# Matrix.net
KiCad netlist of a schematic drawn in Altium Designer
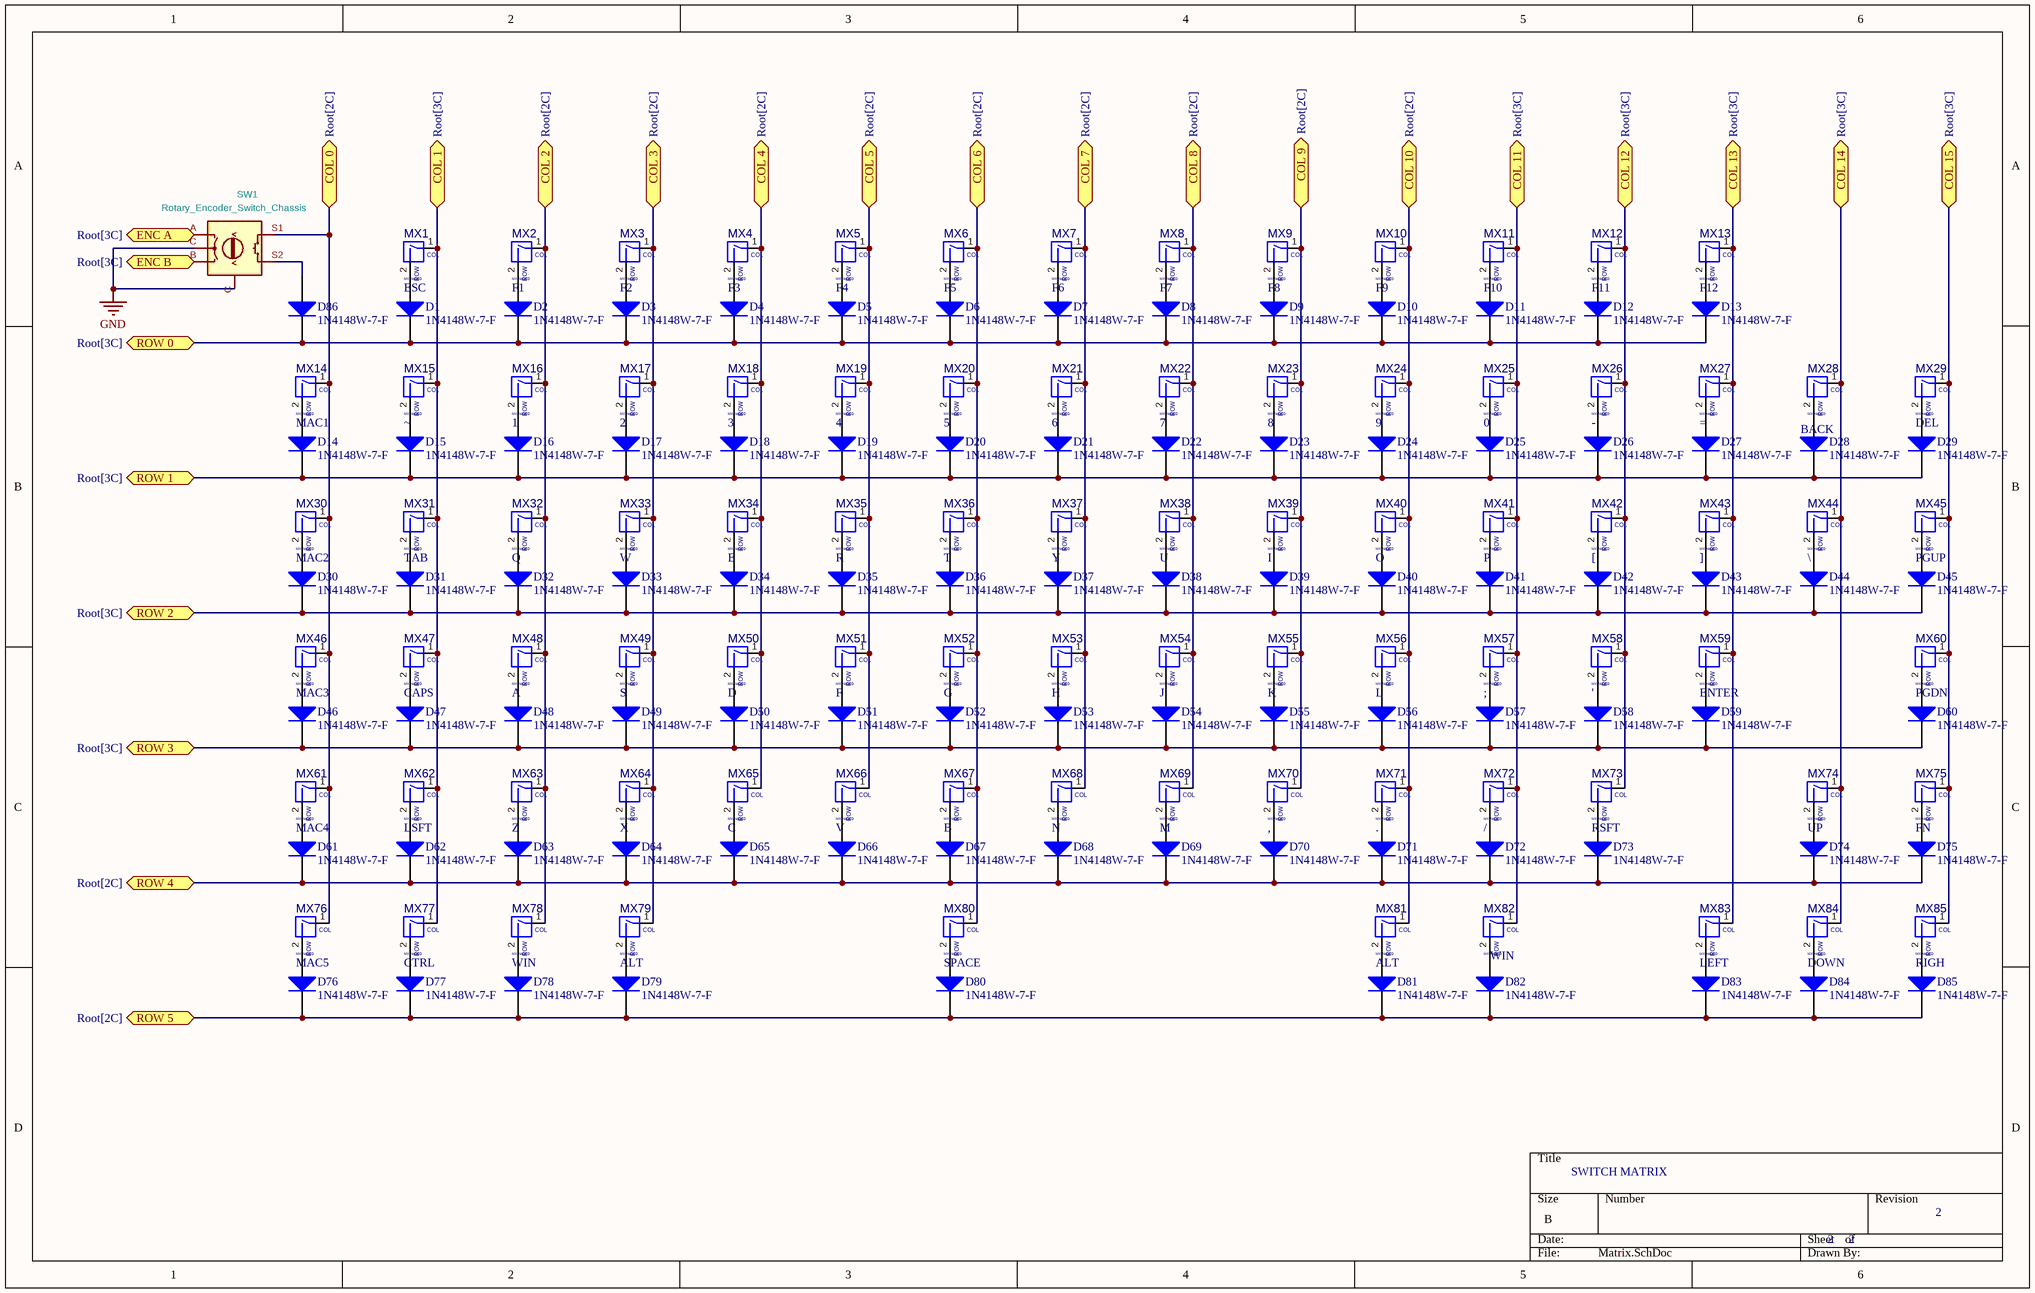
[diagram p0: Matrix.SchDoc]

(export (version "E")
  (design (tool "Eeschema 10.0.6"))
  (components
    (comp (ref "D1")
      (value "1N4148W-7-F")
      (footprint "DIOD-SOD123-2_V")
      (description "Rectifier Diode, 1 Phase, 1 Element, 0.15A, 100V V(RRM), Silicon")
      (libsource (lib "Daniel Hai") (part "D-AK-2"))
    )
    (comp (ref "D2")
      (value "1N4148W-7-F")
      (footprint "DIOD-SOD123-2_V")
      (description "Rectifier Diode, 1 Phase, 1 Element, 0.15A, 100V V(RRM), Silicon")
      (libsource (lib "Daniel Hai") (part "D-AK-2"))
    )
    (comp (ref "D3")
      (value "1N4148W-7-F")
      (footprint "DIOD-SOD123-2_V")
      (description "Rectifier Diode, 1 Phase, 1 Element, 0.15A, 100V V(RRM), Silicon")
      (libsource (lib "Daniel Hai") (part "D-AK-2"))
    )
    (comp (ref "D4")
      (value "1N4148W-7-F")
      (footprint "DIOD-SOD123-2_V")
      (description "Rectifier Diode, 1 Phase, 1 Element, 0.15A, 100V V(RRM), Silicon")
      (libsource (lib "Daniel Hai") (part "D-AK-2"))
    )
    (comp (ref "D5")
      (value "1N4148W-7-F")
      (footprint "DIOD-SOD123-2_V")
      (description "Rectifier Diode, 1 Phase, 1 Element, 0.15A, 100V V(RRM), Silicon")
      (libsource (lib "Daniel Hai") (part "D-AK-2"))
    )
    (comp (ref "D6")
      (value "1N4148W-7-F")
      (footprint "DIOD-SOD123-2_V")
      (description "Rectifier Diode, 1 Phase, 1 Element, 0.15A, 100V V(RRM), Silicon")
      (libsource (lib "Daniel Hai") (part "D-AK-2"))
    )
    (comp (ref "D7")
      (value "1N4148W-7-F")
      (footprint "DIOD-SOD123-2_V")
      (description "Rectifier Diode, 1 Phase, 1 Element, 0.15A, 100V V(RRM), Silicon")
      (libsource (lib "Daniel Hai") (part "D-AK-2"))
    )
    (comp (ref "D8")
      (value "1N4148W-7-F")
      (footprint "DIOD-SOD123-2_V")
      (description "Rectifier Diode, 1 Phase, 1 Element, 0.15A, 100V V(RRM), Silicon")
      (libsource (lib "Daniel Hai") (part "D-AK-2"))
    )
    (comp (ref "D9")
      (value "1N4148W-7-F")
      (footprint "DIOD-SOD123-2_V")
      (description "Rectifier Diode, 1 Phase, 1 Element, 0.15A, 100V V(RRM), Silicon")
      (libsource (lib "Daniel Hai") (part "D-AK-2"))
    )
    (comp (ref "D10")
      (value "1N4148W-7-F")
      (footprint "DIOD-SOD123-2_V")
      (description "Rectifier Diode, 1 Phase, 1 Element, 0.15A, 100V V(RRM), Silicon")
      (libsource (lib "Daniel Hai") (part "D-AK-2"))
    )
    (comp (ref "D11")
      (value "1N4148W-7-F")
      (footprint "DIOD-SOD123-2_V")
      (description "Rectifier Diode, 1 Phase, 1 Element, 0.15A, 100V V(RRM), Silicon")
      (libsource (lib "Daniel Hai") (part "D-AK-2"))
    )
    (comp (ref "D12")
      (value "1N4148W-7-F")
      (footprint "DIOD-SOD123-2_V")
      (description "Rectifier Diode, 1 Phase, 1 Element, 0.15A, 100V V(RRM), Silicon")
      (libsource (lib "Daniel Hai") (part "D-AK-2"))
    )
    (comp (ref "D13")
      (value "1N4148W-7-F")
      (footprint "DIOD-SOD123-2_V")
      (description "Rectifier Diode, 1 Phase, 1 Element, 0.15A, 100V V(RRM), Silicon")
      (libsource (lib "Daniel Hai") (part "D-AK-2"))
    )
    (comp (ref "D14")
      (value "1N4148W-7-F")
      (footprint "DIOD-SOD123-2_V")
      (description "Rectifier Diode, 1 Phase, 1 Element, 0.15A, 100V V(RRM), Silicon")
      (libsource (lib "Daniel Hai") (part "D-AK-2"))
    )
    (comp (ref "D15")
      (value "1N4148W-7-F")
      (footprint "DIOD-SOD123-2_V")
      (description "Rectifier Diode, 1 Phase, 1 Element, 0.15A, 100V V(RRM), Silicon")
      (libsource (lib "Daniel Hai") (part "D-AK-2"))
    )
    (comp (ref "D16")
      (value "1N4148W-7-F")
      (footprint "DIOD-SOD123-2_V")
      (description "Rectifier Diode, 1 Phase, 1 Element, 0.15A, 100V V(RRM), Silicon")
      (libsource (lib "Daniel Hai") (part "D-AK-2"))
    )
    (comp (ref "D17")
      (value "1N4148W-7-F")
      (footprint "DIOD-SOD123-2_V")
      (description "Rectifier Diode, 1 Phase, 1 Element, 0.15A, 100V V(RRM), Silicon")
      (libsource (lib "Daniel Hai") (part "D-AK-2"))
    )
    (comp (ref "D18")
      (value "1N4148W-7-F")
      (footprint "DIOD-SOD123-2_V")
      (description "Rectifier Diode, 1 Phase, 1 Element, 0.15A, 100V V(RRM), Silicon")
      (libsource (lib "Daniel Hai") (part "D-AK-2"))
    )
    (comp (ref "D19")
      (value "1N4148W-7-F")
      (footprint "DIOD-SOD123-2_V")
      (description "Rectifier Diode, 1 Phase, 1 Element, 0.15A, 100V V(RRM), Silicon")
      (libsource (lib "Daniel Hai") (part "D-AK-2"))
    )
    (comp (ref "D20")
      (value "1N4148W-7-F")
      (footprint "DIOD-SOD123-2_V")
      (description "Rectifier Diode, 1 Phase, 1 Element, 0.15A, 100V V(RRM), Silicon")
      (libsource (lib "Daniel Hai") (part "D-AK-2"))
    )
    (comp (ref "D21")
      (value "1N4148W-7-F")
      (footprint "DIOD-SOD123-2_V")
      (description "Rectifier Diode, 1 Phase, 1 Element, 0.15A, 100V V(RRM), Silicon")
      (libsource (lib "Daniel Hai") (part "D-AK-2"))
    )
    (comp (ref "D22")
      (value "1N4148W-7-F")
      (footprint "DIOD-SOD123-2_V")
      (description "Rectifier Diode, 1 Phase, 1 Element, 0.15A, 100V V(RRM), Silicon")
      (libsource (lib "Daniel Hai") (part "D-AK-2"))
    )
    (comp (ref "D23")
      (value "1N4148W-7-F")
      (footprint "DIOD-SOD123-2_V")
      (description "Rectifier Diode, 1 Phase, 1 Element, 0.15A, 100V V(RRM), Silicon")
      (libsource (lib "Daniel Hai") (part "D-AK-2"))
    )
    (comp (ref "D24")
      (value "1N4148W-7-F")
      (footprint "DIOD-SOD123-2_V")
      (description "Rectifier Diode, 1 Phase, 1 Element, 0.15A, 100V V(RRM), Silicon")
      (libsource (lib "Daniel Hai") (part "D-AK-2"))
    )
    (comp (ref "D25")
      (value "1N4148W-7-F")
      (footprint "DIOD-SOD123-2_V")
      (description "Rectifier Diode, 1 Phase, 1 Element, 0.15A, 100V V(RRM), Silicon")
      (libsource (lib "Daniel Hai") (part "D-AK-2"))
    )
    (comp (ref "D26")
      (value "1N4148W-7-F")
      (footprint "DIOD-SOD123-2_V")
      (description "Rectifier Diode, 1 Phase, 1 Element, 0.15A, 100V V(RRM), Silicon")
      (libsource (lib "Daniel Hai") (part "D-AK-2"))
    )
    (comp (ref "D27")
      (value "1N4148W-7-F")
      (footprint "DIOD-SOD123-2_V")
      (description "Rectifier Diode, 1 Phase, 1 Element, 0.15A, 100V V(RRM), Silicon")
      (libsource (lib "Daniel Hai") (part "D-AK-2"))
    )
    (comp (ref "D28")
      (value "1N4148W-7-F")
      (footprint "DIOD-SOD123-2_V")
      (description "Rectifier Diode, 1 Phase, 1 Element, 0.15A, 100V V(RRM), Silicon")
      (libsource (lib "Daniel Hai") (part "D-AK-2"))
    )
    (comp (ref "D29")
      (value "1N4148W-7-F")
      (footprint "DIOD-SOD123-2_V")
      (description "Rectifier Diode, 1 Phase, 1 Element, 0.15A, 100V V(RRM), Silicon")
      (libsource (lib "Daniel Hai") (part "D-AK-2"))
    )
    (comp (ref "D30")
      (value "1N4148W-7-F")
      (footprint "DIOD-SOD123-2_V")
      (description "Rectifier Diode, 1 Phase, 1 Element, 0.15A, 100V V(RRM), Silicon")
      (libsource (lib "Daniel Hai") (part "D-AK-2"))
    )
    (comp (ref "D31")
      (value "1N4148W-7-F")
      (footprint "DIOD-SOD123-2_V")
      (description "Rectifier Diode, 1 Phase, 1 Element, 0.15A, 100V V(RRM), Silicon")
      (libsource (lib "Daniel Hai") (part "D-AK-2"))
    )
    (comp (ref "D32")
      (value "1N4148W-7-F")
      (footprint "DIOD-SOD123-2_V")
      (description "Rectifier Diode, 1 Phase, 1 Element, 0.15A, 100V V(RRM), Silicon")
      (libsource (lib "Daniel Hai") (part "D-AK-2"))
    )
    (comp (ref "D33")
      (value "1N4148W-7-F")
      (footprint "DIOD-SOD123-2_V")
      (description "Rectifier Diode, 1 Phase, 1 Element, 0.15A, 100V V(RRM), Silicon")
      (libsource (lib "Daniel Hai") (part "D-AK-2"))
    )
    (comp (ref "D34")
      (value "1N4148W-7-F")
      (footprint "DIOD-SOD123-2_V")
      (description "Rectifier Diode, 1 Phase, 1 Element, 0.15A, 100V V(RRM), Silicon")
      (libsource (lib "Daniel Hai") (part "D-AK-2"))
    )
    (comp (ref "D35")
      (value "1N4148W-7-F")
      (footprint "DIOD-SOD123-2_V")
      (description "Rectifier Diode, 1 Phase, 1 Element, 0.15A, 100V V(RRM), Silicon")
      (libsource (lib "Daniel Hai") (part "D-AK-2"))
    )
    (comp (ref "D36")
      (value "1N4148W-7-F")
      (footprint "DIOD-SOD123-2_V")
      (description "Rectifier Diode, 1 Phase, 1 Element, 0.15A, 100V V(RRM), Silicon")
      (libsource (lib "Daniel Hai") (part "D-AK-2"))
    )
    (comp (ref "D37")
      (value "1N4148W-7-F")
      (footprint "DIOD-SOD123-2_V")
      (description "Rectifier Diode, 1 Phase, 1 Element, 0.15A, 100V V(RRM), Silicon")
      (libsource (lib "Daniel Hai") (part "D-AK-2"))
    )
    (comp (ref "D38")
      (value "1N4148W-7-F")
      (footprint "DIOD-SOD123-2_V")
      (description "Rectifier Diode, 1 Phase, 1 Element, 0.15A, 100V V(RRM), Silicon")
      (libsource (lib "Daniel Hai") (part "D-AK-2"))
    )
    (comp (ref "D39")
      (value "1N4148W-7-F")
      (footprint "DIOD-SOD123-2_V")
      (description "Rectifier Diode, 1 Phase, 1 Element, 0.15A, 100V V(RRM), Silicon")
      (libsource (lib "Daniel Hai") (part "D-AK-2"))
    )
    (comp (ref "D40")
      (value "1N4148W-7-F")
      (footprint "DIOD-SOD123-2_V")
      (description "Rectifier Diode, 1 Phase, 1 Element, 0.15A, 100V V(RRM), Silicon")
      (libsource (lib "Daniel Hai") (part "D-AK-2"))
    )
    (comp (ref "D41")
      (value "1N4148W-7-F")
      (footprint "DIOD-SOD123-2_V")
      (description "Rectifier Diode, 1 Phase, 1 Element, 0.15A, 100V V(RRM), Silicon")
      (libsource (lib "Daniel Hai") (part "D-AK-2"))
    )
    (comp (ref "D42")
      (value "1N4148W-7-F")
      (footprint "DIOD-SOD123-2_V")
      (description "Rectifier Diode, 1 Phase, 1 Element, 0.15A, 100V V(RRM), Silicon")
      (libsource (lib "Daniel Hai") (part "D-AK-2"))
    )
    (comp (ref "D43")
      (value "1N4148W-7-F")
      (footprint "DIOD-SOD123-2_V")
      (description "Rectifier Diode, 1 Phase, 1 Element, 0.15A, 100V V(RRM), Silicon")
      (libsource (lib "Daniel Hai") (part "D-AK-2"))
    )
    (comp (ref "D44")
      (value "1N4148W-7-F")
      (footprint "DIOD-SOD123-2_V")
      (description "Rectifier Diode, 1 Phase, 1 Element, 0.15A, 100V V(RRM), Silicon")
      (libsource (lib "Daniel Hai") (part "D-AK-2"))
    )
    (comp (ref "D45")
      (value "1N4148W-7-F")
      (footprint "DIOD-SOD123-2_V")
      (description "Rectifier Diode, 1 Phase, 1 Element, 0.15A, 100V V(RRM), Silicon")
      (libsource (lib "Daniel Hai") (part "D-AK-2"))
    )
    (comp (ref "D46")
      (value "1N4148W-7-F")
      (footprint "DIOD-SOD123-2_V")
      (description "Rectifier Diode, 1 Phase, 1 Element, 0.15A, 100V V(RRM), Silicon")
      (libsource (lib "Daniel Hai") (part "D-AK-2"))
    )
    (comp (ref "D47")
      (value "1N4148W-7-F")
      (footprint "DIOD-SOD123-2_V")
      (description "Rectifier Diode, 1 Phase, 1 Element, 0.15A, 100V V(RRM), Silicon")
      (libsource (lib "Daniel Hai") (part "D-AK-2"))
    )
    (comp (ref "D48")
      (value "1N4148W-7-F")
      (footprint "DIOD-SOD123-2_V")
      (description "Rectifier Diode, 1 Phase, 1 Element, 0.15A, 100V V(RRM), Silicon")
      (libsource (lib "Daniel Hai") (part "D-AK-2"))
    )
    (comp (ref "D49")
      (value "1N4148W-7-F")
      (footprint "DIOD-SOD123-2_V")
      (description "Rectifier Diode, 1 Phase, 1 Element, 0.15A, 100V V(RRM), Silicon")
      (libsource (lib "Daniel Hai") (part "D-AK-2"))
    )
    (comp (ref "D50")
      (value "1N4148W-7-F")
      (footprint "DIOD-SOD123-2_V")
      (description "Rectifier Diode, 1 Phase, 1 Element, 0.15A, 100V V(RRM), Silicon")
      (libsource (lib "Daniel Hai") (part "D-AK-2"))
    )
    (comp (ref "D51")
      (value "1N4148W-7-F")
      (footprint "DIOD-SOD123-2_V")
      (description "Rectifier Diode, 1 Phase, 1 Element, 0.15A, 100V V(RRM), Silicon")
      (libsource (lib "Daniel Hai") (part "D-AK-2"))
    )
    (comp (ref "D52")
      (value "1N4148W-7-F")
      (footprint "DIOD-SOD123-2_V")
      (description "Rectifier Diode, 1 Phase, 1 Element, 0.15A, 100V V(RRM), Silicon")
      (libsource (lib "Daniel Hai") (part "D-AK-2"))
    )
    (comp (ref "D53")
      (value "1N4148W-7-F")
      (footprint "DIOD-SOD123-2_V")
      (description "Rectifier Diode, 1 Phase, 1 Element, 0.15A, 100V V(RRM), Silicon")
      (libsource (lib "Daniel Hai") (part "D-AK-2"))
    )
    (comp (ref "D54")
      (value "1N4148W-7-F")
      (footprint "DIOD-SOD123-2_V")
      (description "Rectifier Diode, 1 Phase, 1 Element, 0.15A, 100V V(RRM), Silicon")
      (libsource (lib "Daniel Hai") (part "D-AK-2"))
    )
    (comp (ref "D55")
      (value "1N4148W-7-F")
      (footprint "DIOD-SOD123-2_V")
      (description "Rectifier Diode, 1 Phase, 1 Element, 0.15A, 100V V(RRM), Silicon")
      (libsource (lib "Daniel Hai") (part "D-AK-2"))
    )
    (comp (ref "D56")
      (value "1N4148W-7-F")
      (footprint "DIOD-SOD123-2_V")
      (description "Rectifier Diode, 1 Phase, 1 Element, 0.15A, 100V V(RRM), Silicon")
      (libsource (lib "Daniel Hai") (part "D-AK-2"))
    )
    (comp (ref "D57")
      (value "1N4148W-7-F")
      (footprint "DIOD-SOD123-2_V")
      (description "Rectifier Diode, 1 Phase, 1 Element, 0.15A, 100V V(RRM), Silicon")
      (libsource (lib "Daniel Hai") (part "D-AK-2"))
    )
    (comp (ref "D58")
      (value "1N4148W-7-F")
      (footprint "DIOD-SOD123-2_V")
      (description "Rectifier Diode, 1 Phase, 1 Element, 0.15A, 100V V(RRM), Silicon")
      (libsource (lib "Daniel Hai") (part "D-AK-2"))
    )
    (comp (ref "D59")
      (value "1N4148W-7-F")
      (footprint "DIOD-SOD123-2_V")
      (description "Rectifier Diode, 1 Phase, 1 Element, 0.15A, 100V V(RRM), Silicon")
      (libsource (lib "Daniel Hai") (part "D-AK-2"))
    )
    (comp (ref "D60")
      (value "1N4148W-7-F")
      (footprint "DIOD-SOD123-2_V")
      (description "Rectifier Diode, 1 Phase, 1 Element, 0.15A, 100V V(RRM), Silicon")
      (libsource (lib "Daniel Hai") (part "D-AK-2"))
    )
    (comp (ref "D61")
      (value "1N4148W-7-F")
      (footprint "DIOD-SOD123-2_V")
      (description "Rectifier Diode, 1 Phase, 1 Element, 0.15A, 100V V(RRM), Silicon")
      (libsource (lib "Daniel Hai") (part "D-AK-2"))
    )
    (comp (ref "D62")
      (value "1N4148W-7-F")
      (footprint "DIOD-SOD123-2_V")
      (description "Rectifier Diode, 1 Phase, 1 Element, 0.15A, 100V V(RRM), Silicon")
      (libsource (lib "Daniel Hai") (part "D-AK-2"))
    )
    (comp (ref "D63")
      (value "1N4148W-7-F")
      (footprint "DIOD-SOD123-2_V")
      (description "Rectifier Diode, 1 Phase, 1 Element, 0.15A, 100V V(RRM), Silicon")
      (libsource (lib "Daniel Hai") (part "D-AK-2"))
    )
    (comp (ref "D64")
      (value "1N4148W-7-F")
      (footprint "DIOD-SOD123-2_V")
      (description "Rectifier Diode, 1 Phase, 1 Element, 0.15A, 100V V(RRM), Silicon")
      (libsource (lib "Daniel Hai") (part "D-AK-2"))
    )
    (comp (ref "D65")
      (value "1N4148W-7-F")
      (footprint "DIOD-SOD123-2_V")
      (description "Rectifier Diode, 1 Phase, 1 Element, 0.15A, 100V V(RRM), Silicon")
      (libsource (lib "Daniel Hai") (part "D-AK-2"))
    )
    (comp (ref "D66")
      (value "1N4148W-7-F")
      (footprint "DIOD-SOD123-2_V")
      (description "Rectifier Diode, 1 Phase, 1 Element, 0.15A, 100V V(RRM), Silicon")
      (libsource (lib "Daniel Hai") (part "D-AK-2"))
    )
    (comp (ref "D67")
      (value "1N4148W-7-F")
      (footprint "DIOD-SOD123-2_V")
      (description "Rectifier Diode, 1 Phase, 1 Element, 0.15A, 100V V(RRM), Silicon")
      (libsource (lib "Daniel Hai") (part "D-AK-2"))
    )
    (comp (ref "D68")
      (value "1N4148W-7-F")
      (footprint "DIOD-SOD123-2_V")
      (description "Rectifier Diode, 1 Phase, 1 Element, 0.15A, 100V V(RRM), Silicon")
      (libsource (lib "Daniel Hai") (part "D-AK-2"))
    )
    (comp (ref "D69")
      (value "1N4148W-7-F")
      (footprint "DIOD-SOD123-2_V")
      (description "Rectifier Diode, 1 Phase, 1 Element, 0.15A, 100V V(RRM), Silicon")
      (libsource (lib "Daniel Hai") (part "D-AK-2"))
    )
    (comp (ref "D70")
      (value "1N4148W-7-F")
      (footprint "DIOD-SOD123-2_V")
      (description "Rectifier Diode, 1 Phase, 1 Element, 0.15A, 100V V(RRM), Silicon")
      (libsource (lib "Daniel Hai") (part "D-AK-2"))
    )
    (comp (ref "D71")
      (value "1N4148W-7-F")
      (footprint "DIOD-SOD123-2_V")
      (description "Rectifier Diode, 1 Phase, 1 Element, 0.15A, 100V V(RRM), Silicon")
      (libsource (lib "Daniel Hai") (part "D-AK-2"))
    )
    (comp (ref "D72")
      (value "1N4148W-7-F")
      (footprint "DIOD-SOD123-2_V")
      (description "Rectifier Diode, 1 Phase, 1 Element, 0.15A, 100V V(RRM), Silicon")
      (libsource (lib "Daniel Hai") (part "D-AK-2"))
    )
    (comp (ref "D73")
      (value "1N4148W-7-F")
      (footprint "DIOD-SOD123-2_V")
      (description "Rectifier Diode, 1 Phase, 1 Element, 0.15A, 100V V(RRM), Silicon")
      (libsource (lib "Daniel Hai") (part "D-AK-2"))
    )
    (comp (ref "D74")
      (value "1N4148W-7-F")
      (footprint "DIOD-SOD123-2_V")
      (description "Rectifier Diode, 1 Phase, 1 Element, 0.15A, 100V V(RRM), Silicon")
      (libsource (lib "Daniel Hai") (part "D-AK-2"))
    )
    (comp (ref "D75")
      (value "1N4148W-7-F")
      (footprint "DIOD-SOD123-2_V")
      (description "Rectifier Diode, 1 Phase, 1 Element, 0.15A, 100V V(RRM), Silicon")
      (libsource (lib "Daniel Hai") (part "D-AK-2"))
    )
    (comp (ref "D76")
      (value "1N4148W-7-F")
      (footprint "DIOD-SOD123-2_V")
      (description "Rectifier Diode, 1 Phase, 1 Element, 0.15A, 100V V(RRM), Silicon")
      (libsource (lib "Daniel Hai") (part "D-AK-2"))
    )
    (comp (ref "D77")
      (value "1N4148W-7-F")
      (footprint "DIOD-SOD123-2_V")
      (description "Rectifier Diode, 1 Phase, 1 Element, 0.15A, 100V V(RRM), Silicon")
      (libsource (lib "Daniel Hai") (part "D-AK-2"))
    )
    (comp (ref "D78")
      (value "1N4148W-7-F")
      (footprint "DIOD-SOD123-2_V")
      (description "Rectifier Diode, 1 Phase, 1 Element, 0.15A, 100V V(RRM), Silicon")
      (libsource (lib "Daniel Hai") (part "D-AK-2"))
    )
    (comp (ref "D79")
      (value "1N4148W-7-F")
      (footprint "DIOD-SOD123-2_V")
      (description "Rectifier Diode, 1 Phase, 1 Element, 0.15A, 100V V(RRM), Silicon")
      (libsource (lib "Daniel Hai") (part "D-AK-2"))
    )
    (comp (ref "D80")
      (value "1N4148W-7-F")
      (footprint "DIOD-SOD123-2_V")
      (description "Rectifier Diode, 1 Phase, 1 Element, 0.15A, 100V V(RRM), Silicon")
      (libsource (lib "Daniel Hai") (part "D-AK-2"))
    )
    (comp (ref "D81")
      (value "1N4148W-7-F")
      (footprint "DIOD-SOD123-2_V")
      (description "Rectifier Diode, 1 Phase, 1 Element, 0.15A, 100V V(RRM), Silicon")
      (libsource (lib "Daniel Hai") (part "D-AK-2"))
    )
    (comp (ref "D82")
      (value "1N4148W-7-F")
      (footprint "DIOD-SOD123-2_V")
      (description "Rectifier Diode, 1 Phase, 1 Element, 0.15A, 100V V(RRM), Silicon")
      (libsource (lib "Daniel Hai") (part "D-AK-2"))
    )
    (comp (ref "D83")
      (value "1N4148W-7-F")
      (footprint "DIOD-SOD123-2_V")
      (description "Rectifier Diode, 1 Phase, 1 Element, 0.15A, 100V V(RRM), Silicon")
      (libsource (lib "Daniel Hai") (part "D-AK-2"))
    )
    (comp (ref "D84")
      (value "1N4148W-7-F")
      (footprint "DIOD-SOD123-2_V")
      (description "Rectifier Diode, 1 Phase, 1 Element, 0.15A, 100V V(RRM), Silicon")
      (libsource (lib "Daniel Hai") (part "D-AK-2"))
    )
    (comp (ref "D85")
      (value "1N4148W-7-F")
      (footprint "DIOD-SOD123-2_V")
      (description "Rectifier Diode, 1 Phase, 1 Element, 0.15A, 100V V(RRM), Silicon")
      (libsource (lib "Daniel Hai") (part "D-AK-2"))
    )
    (comp (ref "D86")
      (value "1N4148W-7-F")
      (footprint "DIOD-SOD123-2_V")
      (description "Rectifier Diode, 1 Phase, 1 Element, 0.15A, 100V V(RRM), Silicon")
      (libsource (lib "Daniel Hai") (part "D-AK-2"))
    )
    (comp (ref "MX1")
      (value "ESC")
      (footprint "MXOnly-1U - duplicate")
      (fields (field (name "ALTIUM_VALUE") "MX-NoLED"))
      (libsource (lib "MX_Alps_Hybrid") (part "MX-NoLED"))
    )
    (comp (ref "MX2")
      (value "F1")
      (footprint "MXOnly-1U - duplicate")
      (fields (field (name "ALTIUM_VALUE") "MX-NoLED"))
      (libsource (lib "MX_Alps_Hybrid") (part "MX-NoLED"))
    )
    (comp (ref "MX3")
      (value "F2")
      (footprint "MXOnly-1U - duplicate")
      (fields (field (name "ALTIUM_VALUE") "MX-NoLED"))
      (libsource (lib "MX_Alps_Hybrid") (part "MX-NoLED"))
    )
    (comp (ref "MX4")
      (value "F3")
      (footprint "MXOnly-1U - duplicate")
      (fields (field (name "ALTIUM_VALUE") "MX-NoLED"))
      (libsource (lib "MX_Alps_Hybrid") (part "MX-NoLED"))
    )
    (comp (ref "MX5")
      (value "F4")
      (footprint "MXOnly-1U - duplicate")
      (fields (field (name "ALTIUM_VALUE") "MX-NoLED"))
      (libsource (lib "MX_Alps_Hybrid") (part "MX-NoLED"))
    )
    (comp (ref "MX6")
      (value "F5")
      (footprint "MXOnly-1U - duplicate")
      (fields (field (name "ALTIUM_VALUE") "MX-NoLED"))
      (libsource (lib "MX_Alps_Hybrid") (part "MX-NoLED"))
    )
    (comp (ref "MX7")
      (value "F6")
      (footprint "MXOnly-1U - duplicate")
      (fields (field (name "ALTIUM_VALUE") "MX-NoLED"))
      (libsource (lib "MX_Alps_Hybrid") (part "MX-NoLED"))
    )
    (comp (ref "MX8")
      (value "F7")
      (footprint "MXOnly-1U - duplicate")
      (fields (field (name "ALTIUM_VALUE") "MX-NoLED"))
      (libsource (lib "MX_Alps_Hybrid") (part "MX-NoLED"))
    )
    (comp (ref "MX9")
      (value "F8")
      (footprint "MXOnly-1U - duplicate")
      (fields (field (name "ALTIUM_VALUE") "MX-NoLED"))
      (libsource (lib "MX_Alps_Hybrid") (part "MX-NoLED"))
    )
    (comp (ref "MX10")
      (value "F9")
      (footprint "MXOnly-1U - duplicate")
      (fields (field (name "ALTIUM_VALUE") "MX-NoLED"))
      (libsource (lib "MX_Alps_Hybrid") (part "MX-NoLED"))
    )
    (comp (ref "MX11")
      (value "F10")
      (footprint "MXOnly-1U - duplicate")
      (fields (field (name "ALTIUM_VALUE") "MX-NoLED"))
      (libsource (lib "MX_Alps_Hybrid") (part "MX-NoLED"))
    )
    (comp (ref "MX12")
      (value "F11")
      (footprint "MXOnly-1U - duplicate")
      (fields (field (name "ALTIUM_VALUE") "MX-NoLED"))
      (libsource (lib "MX_Alps_Hybrid") (part "MX-NoLED"))
    )
    (comp (ref "MX13")
      (value "F12")
      (footprint "MXOnly-1U - duplicate")
      (fields (field (name "ALTIUM_VALUE") "MX-NoLED"))
      (libsource (lib "MX_Alps_Hybrid") (part "MX-NoLED"))
    )
    (comp (ref "MX14")
      (value "MAC1")
      (footprint "MXOnly-1U - duplicate")
      (fields (field (name "ALTIUM_VALUE") "MX-NoLED"))
      (libsource (lib "MX_Alps_Hybrid") (part "MX-NoLED"))
    )
    (comp (ref "MX15")
      (value "MX-NoLED")
      (footprint "MXOnly-1U - duplicate")
      (libsource (lib "MX_Alps_Hybrid") (part "MX-NoLED"))
    )
    (comp (ref "MX16")
      (value "1")
      (footprint "MXOnly-1U - duplicate")
      (fields (field (name "ALTIUM_VALUE") "MX-NoLED"))
      (libsource (lib "MX_Alps_Hybrid") (part "MX-NoLED"))
    )
    (comp (ref "MX17")
      (value "2")
      (footprint "MXOnly-1U - duplicate")
      (fields (field (name "ALTIUM_VALUE") "MX-NoLED"))
      (libsource (lib "MX_Alps_Hybrid") (part "MX-NoLED"))
    )
    (comp (ref "MX18")
      (value "3")
      (footprint "MXOnly-1U - duplicate")
      (fields (field (name "ALTIUM_VALUE") "MX-NoLED"))
      (libsource (lib "MX_Alps_Hybrid") (part "MX-NoLED"))
    )
    (comp (ref "MX19")
      (value "4")
      (footprint "MXOnly-1U - duplicate")
      (fields (field (name "ALTIUM_VALUE") "MX-NoLED"))
      (libsource (lib "MX_Alps_Hybrid") (part "MX-NoLED"))
    )
    (comp (ref "MX20")
      (value "5")
      (footprint "MXOnly-1U - duplicate")
      (fields (field (name "ALTIUM_VALUE") "MX-NoLED"))
      (libsource (lib "MX_Alps_Hybrid") (part "MX-NoLED"))
    )
    (comp (ref "MX21")
      (value "6")
      (footprint "MXOnly-1U - duplicate")
      (fields (field (name "ALTIUM_VALUE") "MX-NoLED"))
      (libsource (lib "MX_Alps_Hybrid") (part "MX-NoLED"))
    )
    (comp (ref "MX22")
      (value "7")
      (footprint "MXOnly-1U - duplicate")
      (fields (field (name "ALTIUM_VALUE") "MX-NoLED"))
      (libsource (lib "MX_Alps_Hybrid") (part "MX-NoLED"))
    )
    (comp (ref "MX23")
      (value "8")
      (footprint "MXOnly-1U - duplicate")
      (fields (field (name "ALTIUM_VALUE") "MX-NoLED"))
      (libsource (lib "MX_Alps_Hybrid") (part "MX-NoLED"))
    )
    (comp (ref "MX24")
      (value "9")
      (footprint "MXOnly-1U - duplicate")
      (fields (field (name "ALTIUM_VALUE") "MX-NoLED"))
      (libsource (lib "MX_Alps_Hybrid") (part "MX-NoLED"))
    )
    (comp (ref "MX25")
      (value "0")
      (footprint "MXOnly-1U - duplicate")
      (fields (field (name "ALTIUM_VALUE") "MX-NoLED"))
      (libsource (lib "MX_Alps_Hybrid") (part "MX-NoLED"))
    )
    (comp (ref "MX26")
      (value "-")
      (footprint "MXOnly-1U - duplicate")
      (fields (field (name "ALTIUM_VALUE") "MX-NoLED"))
      (libsource (lib "MX_Alps_Hybrid") (part "MX-NoLED"))
    )
    (comp (ref "MX27")
      (value "MX-NoLED")
      (footprint "MXOnly-1U - duplicate")
      (libsource (lib "MX_Alps_Hybrid") (part "MX-NoLED"))
    )
    (comp (ref "MX28")
      (value "BACK")
      (footprint "MXOnly-2U - duplicate")
      (fields (field (name "ALTIUM_VALUE") "MX-NoLED"))
      (libsource (lib "MX_Alps_Hybrid") (part "MX-NoLED"))
    )
    (comp (ref "MX29")
      (value "DEL")
      (footprint "MXOnly-1U - duplicate")
      (fields (field (name "ALTIUM_VALUE") "MX-NoLED"))
      (libsource (lib "MX_Alps_Hybrid") (part "MX-NoLED"))
    )
    (comp (ref "MX30")
      (value "MAC2")
      (footprint "MXOnly-1U - duplicate")
      (fields (field (name "ALTIUM_VALUE") "MX-NoLED"))
      (libsource (lib "MX_Alps_Hybrid") (part "MX-NoLED"))
    )
    (comp (ref "MX31")
      (value "TAB")
      (footprint "MXOnly-1.5U - duplicate")
      (fields (field (name "ALTIUM_VALUE") "MX-NoLED"))
      (libsource (lib "MX_Alps_Hybrid") (part "MX-NoLED"))
    )
    (comp (ref "MX32")
      (value "Q")
      (footprint "MXOnly-1U - duplicate")
      (fields (field (name "ALTIUM_VALUE") "MX-NoLED"))
      (libsource (lib "MX_Alps_Hybrid") (part "MX-NoLED"))
    )
    (comp (ref "MX33")
      (value "W")
      (footprint "MXOnly-1U - duplicate")
      (fields (field (name "ALTIUM_VALUE") "MX-NoLED"))
      (libsource (lib "MX_Alps_Hybrid") (part "MX-NoLED"))
    )
    (comp (ref "MX34")
      (value "E")
      (footprint "MXOnly-1U - duplicate")
      (fields (field (name "ALTIUM_VALUE") "MX-NoLED"))
      (libsource (lib "MX_Alps_Hybrid") (part "MX-NoLED"))
    )
    (comp (ref "MX35")
      (value "R")
      (footprint "MXOnly-1U - duplicate")
      (fields (field (name "ALTIUM_VALUE") "MX-NoLED"))
      (libsource (lib "MX_Alps_Hybrid") (part "MX-NoLED"))
    )
    (comp (ref "MX36")
      (value "T")
      (footprint "MXOnly-1U - duplicate")
      (fields (field (name "ALTIUM_VALUE") "MX-NoLED"))
      (libsource (lib "MX_Alps_Hybrid") (part "MX-NoLED"))
    )
    (comp (ref "MX37")
      (value "Y")
      (footprint "MXOnly-1U - duplicate")
      (fields (field (name "ALTIUM_VALUE") "MX-NoLED"))
      (libsource (lib "MX_Alps_Hybrid") (part "MX-NoLED"))
    )
    (comp (ref "MX38")
      (value "U")
      (footprint "MXOnly-1U - duplicate")
      (fields (field (name "ALTIUM_VALUE") "MX-NoLED"))
      (libsource (lib "MX_Alps_Hybrid") (part "MX-NoLED"))
    )
    (comp (ref "MX39")
      (value "I")
      (footprint "MXOnly-1U - duplicate")
      (fields (field (name "ALTIUM_VALUE") "MX-NoLED"))
      (libsource (lib "MX_Alps_Hybrid") (part "MX-NoLED"))
    )
    (comp (ref "MX40")
      (value "O")
      (footprint "MXOnly-1U - duplicate")
      (fields (field (name "ALTIUM_VALUE") "MX-NoLED"))
      (libsource (lib "MX_Alps_Hybrid") (part "MX-NoLED"))
    )
    (comp (ref "MX41")
      (value "P")
      (footprint "MXOnly-1U - duplicate")
      (fields (field (name "ALTIUM_VALUE") "MX-NoLED"))
      (libsource (lib "MX_Alps_Hybrid") (part "MX-NoLED"))
    )
    (comp (ref "MX42")
      (value "[")
      (footprint "MXOnly-1U - duplicate")
      (fields (field (name "ALTIUM_VALUE") "MX-NoLED"))
      (libsource (lib "MX_Alps_Hybrid") (part "MX-NoLED"))
    )
    (comp (ref "MX43")
      (value "]")
      (footprint "MXOnly-1U - duplicate")
      (fields (field (name "ALTIUM_VALUE") "MX-NoLED"))
      (libsource (lib "MX_Alps_Hybrid") (part "MX-NoLED"))
    )
    (comp (ref "MX44")
      (value "MX-NoLED")
      (footprint "MXOnly-1.5U - duplicate")
      (libsource (lib "MX_Alps_Hybrid") (part "MX-NoLED"))
    )
    (comp (ref "MX45")
      (value "PGUP")
      (footprint "MXOnly-1U - duplicate")
      (fields (field (name "ALTIUM_VALUE") "MX-NoLED"))
      (libsource (lib "MX_Alps_Hybrid") (part "MX-NoLED"))
    )
    (comp (ref "MX46")
      (value "MAC3")
      (footprint "MXOnly-1U - duplicate")
      (fields (field (name "ALTIUM_VALUE") "MX-NoLED"))
      (libsource (lib "MX_Alps_Hybrid") (part "MX-NoLED"))
    )
    (comp (ref "MX47")
      (value "CAPS")
      (footprint "MXOnly-1.75U - duplicate")
      (fields (field (name "ALTIUM_VALUE") "MX-NoLED"))
      (libsource (lib "MX_Alps_Hybrid") (part "MX-NoLED"))
    )
    (comp (ref "MX48")
      (value "A")
      (footprint "MXOnly-1U - duplicate")
      (fields (field (name "ALTIUM_VALUE") "MX-NoLED"))
      (libsource (lib "MX_Alps_Hybrid") (part "MX-NoLED"))
    )
    (comp (ref "MX49")
      (value "S")
      (footprint "MXOnly-1U - duplicate")
      (fields (field (name "ALTIUM_VALUE") "MX-NoLED"))
      (libsource (lib "MX_Alps_Hybrid") (part "MX-NoLED"))
    )
    (comp (ref "MX50")
      (value "D")
      (footprint "MXOnly-1U - duplicate")
      (fields (field (name "ALTIUM_VALUE") "MX-NoLED"))
      (libsource (lib "MX_Alps_Hybrid") (part "MX-NoLED"))
    )
    (comp (ref "MX51")
      (value "F")
      (footprint "MXOnly-1U - duplicate")
      (fields (field (name "ALTIUM_VALUE") "MX-NoLED"))
      (libsource (lib "MX_Alps_Hybrid") (part "MX-NoLED"))
    )
    (comp (ref "MX52")
      (value "G")
      (footprint "MXOnly-1U - duplicate")
      (fields (field (name "ALTIUM_VALUE") "MX-NoLED"))
      (libsource (lib "MX_Alps_Hybrid") (part "MX-NoLED"))
    )
    (comp (ref "MX53")
      (value "H")
      (footprint "MXOnly-1U - duplicate")
      (fields (field (name "ALTIUM_VALUE") "MX-NoLED"))
      (libsource (lib "MX_Alps_Hybrid") (part "MX-NoLED"))
    )
    (comp (ref "MX54")
      (value "J")
      (footprint "MXOnly-1U - duplicate")
      (fields (field (name "ALTIUM_VALUE") "MX-NoLED"))
      (libsource (lib "MX_Alps_Hybrid") (part "MX-NoLED"))
    )
    (comp (ref "MX55")
      (value "K")
      (footprint "MXOnly-1U - duplicate")
      (fields (field (name "ALTIUM_VALUE") "MX-NoLED"))
      (libsource (lib "MX_Alps_Hybrid") (part "MX-NoLED"))
    )
    (comp (ref "MX56")
      (value "L")
      (footprint "MXOnly-1U - duplicate")
      (fields (field (name "ALTIUM_VALUE") "MX-NoLED"))
      (libsource (lib "MX_Alps_Hybrid") (part "MX-NoLED"))
    )
    (comp (ref "MX57")
      (value ";")
      (footprint "MXOnly-1U - duplicate")
      (fields (field (name "ALTIUM_VALUE") "MX-NoLED"))
      (libsource (lib "MX_Alps_Hybrid") (part "MX-NoLED"))
    )
    (comp (ref "MX58")
      (value "'")
      (footprint "MXOnly-1U - duplicate")
      (fields (field (name "ALTIUM_VALUE") "MX-NoLED"))
      (libsource (lib "MX_Alps_Hybrid") (part "MX-NoLED"))
    )
    (comp (ref "MX59")
      (value "ENTER")
      (footprint "MXOnly-2.25U - duplicate")
      (fields (field (name "ALTIUM_VALUE") "MX-NoLED"))
      (libsource (lib "MX_Alps_Hybrid") (part "MX-NoLED"))
    )
    (comp (ref "MX60")
      (value "PGDN")
      (footprint "MXOnly-1U - duplicate")
      (fields (field (name "ALTIUM_VALUE") "MX-NoLED"))
      (libsource (lib "MX_Alps_Hybrid") (part "MX-NoLED"))
    )
    (comp (ref "MX61")
      (value "MAC4")
      (footprint "MXOnly-1U - duplicate")
      (fields (field (name "ALTIUM_VALUE") "MX-NoLED"))
      (libsource (lib "MX_Alps_Hybrid") (part "MX-NoLED"))
    )
    (comp (ref "MX62")
      (value "LSFT")
      (footprint "MXOnly-2.25U - duplicate")
      (fields (field (name "ALTIUM_VALUE") "MX-NoLED"))
      (libsource (lib "MX_Alps_Hybrid") (part "MX-NoLED"))
    )
    (comp (ref "MX63")
      (value "Z")
      (footprint "MXOnly-1U - duplicate")
      (fields (field (name "ALTIUM_VALUE") "MX-NoLED"))
      (libsource (lib "MX_Alps_Hybrid") (part "MX-NoLED"))
    )
    (comp (ref "MX64")
      (value "X")
      (footprint "MXOnly-1U - duplicate")
      (fields (field (name "ALTIUM_VALUE") "MX-NoLED"))
      (libsource (lib "MX_Alps_Hybrid") (part "MX-NoLED"))
    )
    (comp (ref "MX65")
      (value "C")
      (footprint "MXOnly-1U - duplicate")
      (fields (field (name "ALTIUM_VALUE") "MX-NoLED"))
      (libsource (lib "MX_Alps_Hybrid") (part "MX-NoLED"))
    )
    (comp (ref "MX66")
      (value "V")
      (footprint "MXOnly-1U - duplicate")
      (fields (field (name "ALTIUM_VALUE") "MX-NoLED"))
      (libsource (lib "MX_Alps_Hybrid") (part "MX-NoLED"))
    )
    (comp (ref "MX67")
      (value "B")
      (footprint "MXOnly-1U - duplicate")
      (fields (field (name "ALTIUM_VALUE") "MX-NoLED"))
      (libsource (lib "MX_Alps_Hybrid") (part "MX-NoLED"))
    )
    (comp (ref "MX68")
      (value "N")
      (footprint "MXOnly-1U - duplicate")
      (fields (field (name "ALTIUM_VALUE") "MX-NoLED"))
      (libsource (lib "MX_Alps_Hybrid") (part "MX-NoLED"))
    )
    (comp (ref "MX69")
      (value "M")
      (footprint "MXOnly-1U - duplicate")
      (fields (field (name "ALTIUM_VALUE") "MX-NoLED"))
      (libsource (lib "MX_Alps_Hybrid") (part "MX-NoLED"))
    )
    (comp (ref "MX70")
      (value ",")
      (footprint "MXOnly-1U - duplicate")
      (fields (field (name "ALTIUM_VALUE") "MX-NoLED"))
      (libsource (lib "MX_Alps_Hybrid") (part "MX-NoLED"))
    )
    (comp (ref "MX71")
      (value ".")
      (footprint "MXOnly-1U - duplicate")
      (fields (field (name "ALTIUM_VALUE") "MX-NoLED"))
      (libsource (lib "MX_Alps_Hybrid") (part "MX-NoLED"))
    )
    (comp (ref "MX72")
      (value "/")
      (footprint "MXOnly-1U - duplicate")
      (fields (field (name "ALTIUM_VALUE") "MX-NoLED"))
      (libsource (lib "MX_Alps_Hybrid") (part "MX-NoLED"))
    )
    (comp (ref "MX73")
      (value "RSFT")
      (footprint "MXOnly-1.75U - duplicate")
      (fields (field (name "ALTIUM_VALUE") "MX-NoLED"))
      (libsource (lib "MX_Alps_Hybrid") (part "MX-NoLED"))
    )
    (comp (ref "MX74")
      (value "UP")
      (footprint "MXOnly-1U - duplicate")
      (fields (field (name "ALTIUM_VALUE") "MX-NoLED"))
      (libsource (lib "MX_Alps_Hybrid") (part "MX-NoLED"))
    )
    (comp (ref "MX75")
      (value "FN")
      (footprint "MXOnly-1U - duplicate")
      (fields (field (name "ALTIUM_VALUE") "MX-NoLED"))
      (libsource (lib "MX_Alps_Hybrid") (part "MX-NoLED"))
    )
    (comp (ref "MX76")
      (value "MAC5")
      (footprint "MXOnly-1U - duplicate")
      (fields (field (name "ALTIUM_VALUE") "MX-NoLED"))
      (libsource (lib "MX_Alps_Hybrid") (part "MX-NoLED"))
    )
    (comp (ref "MX77")
      (value "CTRL")
      (footprint "MXOnly-1.25U - duplicate")
      (fields (field (name "ALTIUM_VALUE") "MX-NoLED"))
      (libsource (lib "MX_Alps_Hybrid") (part "MX-NoLED"))
    )
    (comp (ref "MX78")
      (value "WIN")
      (footprint "MXOnly-1.25U - duplicate")
      (fields (field (name "ALTIUM_VALUE") "MX-NoLED"))
      (libsource (lib "MX_Alps_Hybrid") (part "MX-NoLED"))
    )
    (comp (ref "MX79")
      (value "ALT")
      (footprint "MXOnly-1.25U - duplicate")
      (fields (field (name "ALTIUM_VALUE") "MX-NoLED"))
      (libsource (lib "MX_Alps_Hybrid") (part "MX-NoLED"))
    )
    (comp (ref "MX80")
      (value "SPACE")
      (footprint "MXOnly-6.25U-ReversedStabilizers - duplicate")
      (fields (field (name "ALTIUM_VALUE") "MX-NoLED"))
      (libsource (lib "MX_Alps_Hybrid") (part "MX-NoLED"))
    )
    (comp (ref "MX81")
      (value "ALT")
      (footprint "MXOnly-1.5U - duplicate")
      (fields (field (name "ALTIUM_VALUE") "MX-NoLED"))
      (libsource (lib "MX_Alps_Hybrid") (part "MX-NoLED"))
    )
    (comp (ref "MX82")
      (value "WIN")
      (footprint "MXOnly-1.5U - duplicate")
      (fields (field (name "ALTIUM_VALUE") "MX-NoLED"))
      (libsource (lib "MX_Alps_Hybrid") (part "MX-NoLED"))
    )
    (comp (ref "MX83")
      (value "LEFT")
      (footprint "MXOnly-1U - duplicate")
      (fields (field (name "ALTIUM_VALUE") "MX-NoLED"))
      (libsource (lib "MX_Alps_Hybrid") (part "MX-NoLED"))
    )
    (comp (ref "MX84")
      (value "DOWN")
      (footprint "MXOnly-1U - duplicate")
      (fields (field (name "ALTIUM_VALUE") "MX-NoLED"))
      (libsource (lib "MX_Alps_Hybrid") (part "MX-NoLED"))
    )
    (comp (ref "MX85")
      (value "RIGH")
      (footprint "MXOnly-1U - duplicate")
      (fields (field (name "ALTIUM_VALUE") "MX-NoLED"))
      (libsource (lib "MX_Alps_Hybrid") (part "MX-NoLED"))
    )
    (comp (ref "SW1")
      (value "Rotary_Encoder_Switch_Chassis")
      (footprint "RotaryEncoder_Alps_EC11E-Switch_Vertical_H20mm")
      (libsource (lib "random-keyboard-parts") (part "Rotary_Encoder_Switch_Chassis"))
    )
  )
  (nets
    (net (code "1") (name "/COL 0") (class "Default")
      (node (ref "MX14") (pin "1") (pinfunction "COL_1") (pintype "passive"))
      (node (ref "MX30") (pin "1") (pinfunction "COL_1") (pintype "passive"))
      (node (ref "MX46") (pin "1") (pinfunction "COL_1") (pintype "passive"))
      (node (ref "MX61") (pin "1") (pinfunction "COL_1") (pintype "passive"))
      (node (ref "MX76") (pin "1") (pinfunction "COL_1") (pintype "passive"))
      (node (ref "SW1") (pin "S1") (pinfunction "S1_S1") (pintype "passive"))
    )
    (net (code "2") (name "/COL 1") (class "Default")
      (node (ref "MX1") (pin "1") (pinfunction "COL_1") (pintype "passive"))
      (node (ref "MX15") (pin "1") (pinfunction "COL_1") (pintype "passive"))
      (node (ref "MX31") (pin "1") (pinfunction "COL_1") (pintype "passive"))
      (node (ref "MX47") (pin "1") (pinfunction "COL_1") (pintype "passive"))
      (node (ref "MX62") (pin "1") (pinfunction "COL_1") (pintype "passive"))
      (node (ref "MX77") (pin "1") (pinfunction "COL_1") (pintype "passive"))
    )
    (net (code "3") (name "/COL 2") (class "Default")
      (node (ref "MX16") (pin "1") (pinfunction "COL_1") (pintype "passive"))
      (node (ref "MX2") (pin "1") (pinfunction "COL_1") (pintype "passive"))
      (node (ref "MX32") (pin "1") (pinfunction "COL_1") (pintype "passive"))
      (node (ref "MX48") (pin "1") (pinfunction "COL_1") (pintype "passive"))
      (node (ref "MX63") (pin "1") (pinfunction "COL_1") (pintype "passive"))
      (node (ref "MX78") (pin "1") (pinfunction "COL_1") (pintype "passive"))
    )
    (net (code "4") (name "/COL 3") (class "Default")
      (node (ref "MX17") (pin "1") (pinfunction "COL_1") (pintype "passive"))
      (node (ref "MX3") (pin "1") (pinfunction "COL_1") (pintype "passive"))
      (node (ref "MX33") (pin "1") (pinfunction "COL_1") (pintype "passive"))
      (node (ref "MX49") (pin "1") (pinfunction "COL_1") (pintype "passive"))
      (node (ref "MX64") (pin "1") (pinfunction "COL_1") (pintype "passive"))
      (node (ref "MX79") (pin "1") (pinfunction "COL_1") (pintype "passive"))
    )
    (net (code "5") (name "/COL 4") (class "Default")
      (node (ref "MX18") (pin "1") (pinfunction "COL_1") (pintype "passive"))
      (node (ref "MX34") (pin "1") (pinfunction "COL_1") (pintype "passive"))
      (node (ref "MX4") (pin "1") (pinfunction "COL_1") (pintype "passive"))
      (node (ref "MX50") (pin "1") (pinfunction "COL_1") (pintype "passive"))
      (node (ref "MX65") (pin "1") (pinfunction "COL_1") (pintype "passive"))
    )
    (net (code "6") (name "/COL 5") (class "Default")
      (node (ref "MX19") (pin "1") (pinfunction "COL_1") (pintype "passive"))
      (node (ref "MX35") (pin "1") (pinfunction "COL_1") (pintype "passive"))
      (node (ref "MX5") (pin "1") (pinfunction "COL_1") (pintype "passive"))
      (node (ref "MX51") (pin "1") (pinfunction "COL_1") (pintype "passive"))
      (node (ref "MX66") (pin "1") (pinfunction "COL_1") (pintype "passive"))
    )
    (net (code "7") (name "/COL 6") (class "Default")
      (node (ref "MX20") (pin "1") (pinfunction "COL_1") (pintype "passive"))
      (node (ref "MX36") (pin "1") (pinfunction "COL_1") (pintype "passive"))
      (node (ref "MX52") (pin "1") (pinfunction "COL_1") (pintype "passive"))
      (node (ref "MX6") (pin "1") (pinfunction "COL_1") (pintype "passive"))
      (node (ref "MX67") (pin "1") (pinfunction "COL_1") (pintype "passive"))
      (node (ref "MX80") (pin "1") (pinfunction "COL_1") (pintype "passive"))
    )
    (net (code "8") (name "/COL 7") (class "Default")
      (node (ref "MX21") (pin "1") (pinfunction "COL_1") (pintype "passive"))
      (node (ref "MX37") (pin "1") (pinfunction "COL_1") (pintype "passive"))
      (node (ref "MX53") (pin "1") (pinfunction "COL_1") (pintype "passive"))
      (node (ref "MX68") (pin "1") (pinfunction "COL_1") (pintype "passive"))
      (node (ref "MX7") (pin "1") (pinfunction "COL_1") (pintype "passive"))
    )
    (net (code "9") (name "/COL 8") (class "Default")
      (node (ref "MX22") (pin "1") (pinfunction "COL_1") (pintype "passive"))
      (node (ref "MX38") (pin "1") (pinfunction "COL_1") (pintype "passive"))
      (node (ref "MX54") (pin "1") (pinfunction "COL_1") (pintype "passive"))
      (node (ref "MX69") (pin "1") (pinfunction "COL_1") (pintype "passive"))
      (node (ref "MX8") (pin "1") (pinfunction "COL_1") (pintype "passive"))
    )
    (net (code "10") (name "/COL 9") (class "Default")
      (node (ref "MX23") (pin "1") (pinfunction "COL_1") (pintype "passive"))
      (node (ref "MX39") (pin "1") (pinfunction "COL_1") (pintype "passive"))
      (node (ref "MX55") (pin "1") (pinfunction "COL_1") (pintype "passive"))
      (node (ref "MX70") (pin "1") (pinfunction "COL_1") (pintype "passive"))
      (node (ref "MX9") (pin "1") (pinfunction "COL_1") (pintype "passive"))
    )
    (net (code "11") (name "/COL 10") (class "Default")
      (node (ref "MX10") (pin "1") (pinfunction "COL_1") (pintype "passive"))
      (node (ref "MX24") (pin "1") (pinfunction "COL_1") (pintype "passive"))
      (node (ref "MX40") (pin "1") (pinfunction "COL_1") (pintype "passive"))
      (node (ref "MX56") (pin "1") (pinfunction "COL_1") (pintype "passive"))
      (node (ref "MX71") (pin "1") (pinfunction "COL_1") (pintype "passive"))
      (node (ref "MX81") (pin "1") (pinfunction "COL_1") (pintype "passive"))
    )
    (net (code "12") (name "/COL 11") (class "Default")
      (node (ref "MX11") (pin "1") (pinfunction "COL_1") (pintype "passive"))
      (node (ref "MX25") (pin "1") (pinfunction "COL_1") (pintype "passive"))
      (node (ref "MX41") (pin "1") (pinfunction "COL_1") (pintype "passive"))
      (node (ref "MX57") (pin "1") (pinfunction "COL_1") (pintype "passive"))
      (node (ref "MX72") (pin "1") (pinfunction "COL_1") (pintype "passive"))
      (node (ref "MX82") (pin "1") (pinfunction "COL_1") (pintype "passive"))
    )
    (net (code "13") (name "/COL 12") (class "Default")
      (node (ref "MX12") (pin "1") (pinfunction "COL_1") (pintype "passive"))
      (node (ref "MX26") (pin "1") (pinfunction "COL_1") (pintype "passive"))
      (node (ref "MX42") (pin "1") (pinfunction "COL_1") (pintype "passive"))
      (node (ref "MX58") (pin "1") (pinfunction "COL_1") (pintype "passive"))
      (node (ref "MX73") (pin "1") (pinfunction "COL_1") (pintype "passive"))
    )
    (net (code "14") (name "/COL 13") (class "Default")
      (node (ref "MX13") (pin "1") (pinfunction "COL_1") (pintype "passive"))
      (node (ref "MX27") (pin "1") (pinfunction "COL_1") (pintype "passive"))
      (node (ref "MX43") (pin "1") (pinfunction "COL_1") (pintype "passive"))
      (node (ref "MX59") (pin "1") (pinfunction "COL_1") (pintype "passive"))
      (node (ref "MX83") (pin "1") (pinfunction "COL_1") (pintype "passive"))
    )
    (net (code "15") (name "/COL 14") (class "Default")
      (node (ref "MX28") (pin "1") (pinfunction "COL_1") (pintype "passive"))
      (node (ref "MX44") (pin "1") (pinfunction "COL_1") (pintype "passive"))
      (node (ref "MX74") (pin "1") (pinfunction "COL_1") (pintype "passive"))
      (node (ref "MX84") (pin "1") (pinfunction "COL_1") (pintype "passive"))
    )
    (net (code "16") (name "/COL 15") (class "Default")
      (node (ref "MX29") (pin "1") (pinfunction "COL_1") (pintype "passive"))
      (node (ref "MX45") (pin "1") (pinfunction "COL_1") (pintype "passive"))
      (node (ref "MX60") (pin "1") (pinfunction "COL_1") (pintype "passive"))
      (node (ref "MX75") (pin "1") (pinfunction "COL_1") (pintype "passive"))
      (node (ref "MX85") (pin "1") (pinfunction "COL_1") (pintype "passive"))
    )
    (net (code "17") (name "/ENC A") (class "Default")
      (node (ref "SW1") (pin "A") (pinfunction "A_A") (pintype "passive"))
    )
    (net (code "18") (name "/ENC B") (class "Default")
      (node (ref "SW1") (pin "B") (pinfunction "B_B") (pintype "passive"))
    )
    (net (code "19") (name "/ROW 0") (class "Default")
      (node (ref "D1") (pin "2") (pinfunction "K_2") (pintype "passive"))
      (node (ref "D10") (pin "2") (pinfunction "K_2") (pintype "passive"))
      (node (ref "D11") (pin "2") (pinfunction "K_2") (pintype "passive"))
      (node (ref "D12") (pin "2") (pinfunction "K_2") (pintype "passive"))
      (node (ref "D13") (pin "2") (pinfunction "K_2") (pintype "passive"))
      (node (ref "D2") (pin "2") (pinfunction "K_2") (pintype "passive"))
      (node (ref "D3") (pin "2") (pinfunction "K_2") (pintype "passive"))
      (node (ref "D4") (pin "2") (pinfunction "K_2") (pintype "passive"))
      (node (ref "D5") (pin "2") (pinfunction "K_2") (pintype "passive"))
      (node (ref "D6") (pin "2") (pinfunction "K_2") (pintype "passive"))
      (node (ref "D7") (pin "2") (pinfunction "K_2") (pintype "passive"))
      (node (ref "D8") (pin "2") (pinfunction "K_2") (pintype "passive"))
      (node (ref "D86") (pin "2") (pinfunction "K_2") (pintype "passive"))
      (node (ref "D9") (pin "2") (pinfunction "K_2") (pintype "passive"))
    )
    (net (code "20") (name "/ROW 1") (class "Default")
      (node (ref "D14") (pin "2") (pinfunction "K_2") (pintype "passive"))
      (node (ref "D15") (pin "2") (pinfunction "K_2") (pintype "passive"))
      (node (ref "D16") (pin "2") (pinfunction "K_2") (pintype "passive"))
      (node (ref "D17") (pin "2") (pinfunction "K_2") (pintype "passive"))
      (node (ref "D18") (pin "2") (pinfunction "K_2") (pintype "passive"))
      (node (ref "D19") (pin "2") (pinfunction "K_2") (pintype "passive"))
      (node (ref "D20") (pin "2") (pinfunction "K_2") (pintype "passive"))
      (node (ref "D21") (pin "2") (pinfunction "K_2") (pintype "passive"))
      (node (ref "D22") (pin "2") (pinfunction "K_2") (pintype "passive"))
      (node (ref "D23") (pin "2") (pinfunction "K_2") (pintype "passive"))
      (node (ref "D24") (pin "2") (pinfunction "K_2") (pintype "passive"))
      (node (ref "D25") (pin "2") (pinfunction "K_2") (pintype "passive"))
      (node (ref "D26") (pin "2") (pinfunction "K_2") (pintype "passive"))
      (node (ref "D27") (pin "2") (pinfunction "K_2") (pintype "passive"))
      (node (ref "D28") (pin "2") (pinfunction "K_2") (pintype "passive"))
      (node (ref "D29") (pin "2") (pinfunction "K_2") (pintype "passive"))
    )
    (net (code "21") (name "/ROW 2") (class "Default")
      (node (ref "D30") (pin "2") (pinfunction "K_2") (pintype "passive"))
      (node (ref "D31") (pin "2") (pinfunction "K_2") (pintype "passive"))
      (node (ref "D32") (pin "2") (pinfunction "K_2") (pintype "passive"))
      (node (ref "D33") (pin "2") (pinfunction "K_2") (pintype "passive"))
      (node (ref "D34") (pin "2") (pinfunction "K_2") (pintype "passive"))
      (node (ref "D35") (pin "2") (pinfunction "K_2") (pintype "passive"))
      (node (ref "D36") (pin "2") (pinfunction "K_2") (pintype "passive"))
      (node (ref "D37") (pin "2") (pinfunction "K_2") (pintype "passive"))
      (node (ref "D38") (pin "2") (pinfunction "K_2") (pintype "passive"))
      (node (ref "D39") (pin "2") (pinfunction "K_2") (pintype "passive"))
      (node (ref "D40") (pin "2") (pinfunction "K_2") (pintype "passive"))
      (node (ref "D41") (pin "2") (pinfunction "K_2") (pintype "passive"))
      (node (ref "D42") (pin "2") (pinfunction "K_2") (pintype "passive"))
      (node (ref "D43") (pin "2") (pinfunction "K_2") (pintype "passive"))
      (node (ref "D44") (pin "2") (pinfunction "K_2") (pintype "passive"))
      (node (ref "D45") (pin "2") (pinfunction "K_2") (pintype "passive"))
    )
    (net (code "22") (name "/ROW 3") (class "Default")
      (node (ref "D46") (pin "2") (pinfunction "K_2") (pintype "passive"))
      (node (ref "D47") (pin "2") (pinfunction "K_2") (pintype "passive"))
      (node (ref "D48") (pin "2") (pinfunction "K_2") (pintype "passive"))
      (node (ref "D49") (pin "2") (pinfunction "K_2") (pintype "passive"))
      (node (ref "D50") (pin "2") (pinfunction "K_2") (pintype "passive"))
      (node (ref "D51") (pin "2") (pinfunction "K_2") (pintype "passive"))
      (node (ref "D52") (pin "2") (pinfunction "K_2") (pintype "passive"))
      (node (ref "D53") (pin "2") (pinfunction "K_2") (pintype "passive"))
      (node (ref "D54") (pin "2") (pinfunction "K_2") (pintype "passive"))
      (node (ref "D55") (pin "2") (pinfunction "K_2") (pintype "passive"))
      (node (ref "D56") (pin "2") (pinfunction "K_2") (pintype "passive"))
      (node (ref "D57") (pin "2") (pinfunction "K_2") (pintype "passive"))
      (node (ref "D58") (pin "2") (pinfunction "K_2") (pintype "passive"))
      (node (ref "D59") (pin "2") (pinfunction "K_2") (pintype "passive"))
      (node (ref "D60") (pin "2") (pinfunction "K_2") (pintype "passive"))
    )
    (net (code "23") (name "/ROW 4") (class "Default")
      (node (ref "D61") (pin "2") (pinfunction "K_2") (pintype "passive"))
      (node (ref "D62") (pin "2") (pinfunction "K_2") (pintype "passive"))
      (node (ref "D63") (pin "2") (pinfunction "K_2") (pintype "passive"))
      (node (ref "D64") (pin "2") (pinfunction "K_2") (pintype "passive"))
      (node (ref "D65") (pin "2") (pinfunction "K_2") (pintype "passive"))
      (node (ref "D66") (pin "2") (pinfunction "K_2") (pintype "passive"))
      (node (ref "D67") (pin "2") (pinfunction "K_2") (pintype "passive"))
      (node (ref "D68") (pin "2") (pinfunction "K_2") (pintype "passive"))
      (node (ref "D69") (pin "2") (pinfunction "K_2") (pintype "passive"))
      (node (ref "D70") (pin "2") (pinfunction "K_2") (pintype "passive"))
      (node (ref "D71") (pin "2") (pinfunction "K_2") (pintype "passive"))
      (node (ref "D72") (pin "2") (pinfunction "K_2") (pintype "passive"))
      (node (ref "D73") (pin "2") (pinfunction "K_2") (pintype "passive"))
      (node (ref "D74") (pin "2") (pinfunction "K_2") (pintype "passive"))
      (node (ref "D75") (pin "2") (pinfunction "K_2") (pintype "passive"))
    )
    (net (code "24") (name "/ROW 5") (class "Default")
      (node (ref "D76") (pin "2") (pinfunction "K_2") (pintype "passive"))
      (node (ref "D77") (pin "2") (pinfunction "K_2") (pintype "passive"))
      (node (ref "D78") (pin "2") (pinfunction "K_2") (pintype "passive"))
      (node (ref "D79") (pin "2") (pinfunction "K_2") (pintype "passive"))
      (node (ref "D80") (pin "2") (pinfunction "K_2") (pintype "passive"))
      (node (ref "D81") (pin "2") (pinfunction "K_2") (pintype "passive"))
      (node (ref "D82") (pin "2") (pinfunction "K_2") (pintype "passive"))
      (node (ref "D83") (pin "2") (pinfunction "K_2") (pintype "passive"))
      (node (ref "D84") (pin "2") (pinfunction "K_2") (pintype "passive"))
      (node (ref "D85") (pin "2") (pinfunction "K_2") (pintype "passive"))
    )
    (net (code "25") (name "GND") (class "Default")
      (node (ref "SW1") (pin "C") (pinfunction "C_C") (pintype "passive"))
    )
    (net (code "26") (name "Net-(D1-A)") (class "Default")
      (node (ref "D1") (pin "1") (pinfunction "A_1") (pintype "passive"))
      (node (ref "MX1") (pin "2") (pinfunction "ROW_2") (pintype "passive"))
    )
    (net (code "27") (name "Net-(D2-A)") (class "Default")
      (node (ref "D2") (pin "1") (pinfunction "A_1") (pintype "passive"))
      (node (ref "MX2") (pin "2") (pinfunction "ROW_2") (pintype "passive"))
    )
    (net (code "28") (name "Net-(D3-A)") (class "Default")
      (node (ref "D3") (pin "1") (pinfunction "A_1") (pintype "passive"))
      (node (ref "MX3") (pin "2") (pinfunction "ROW_2") (pintype "passive"))
    )
    (net (code "29") (name "Net-(D4-A)") (class "Default")
      (node (ref "D4") (pin "1") (pinfunction "A_1") (pintype "passive"))
      (node (ref "MX4") (pin "2") (pinfunction "ROW_2") (pintype "passive"))
    )
    (net (code "30") (name "Net-(D5-A)") (class "Default")
      (node (ref "D5") (pin "1") (pinfunction "A_1") (pintype "passive"))
      (node (ref "MX5") (pin "2") (pinfunction "ROW_2") (pintype "passive"))
    )
    (net (code "31") (name "Net-(D6-A)") (class "Default")
      (node (ref "D6") (pin "1") (pinfunction "A_1") (pintype "passive"))
      (node (ref "MX6") (pin "2") (pinfunction "ROW_2") (pintype "passive"))
    )
    (net (code "32") (name "Net-(D7-A)") (class "Default")
      (node (ref "D7") (pin "1") (pinfunction "A_1") (pintype "passive"))
      (node (ref "MX7") (pin "2") (pinfunction "ROW_2") (pintype "passive"))
    )
    (net (code "33") (name "Net-(D8-A)") (class "Default")
      (node (ref "D8") (pin "1") (pinfunction "A_1") (pintype "passive"))
      (node (ref "MX8") (pin "2") (pinfunction "ROW_2") (pintype "passive"))
    )
    (net (code "34") (name "Net-(D9-A)") (class "Default")
      (node (ref "D9") (pin "1") (pinfunction "A_1") (pintype "passive"))
      (node (ref "MX9") (pin "2") (pinfunction "ROW_2") (pintype "passive"))
    )
    (net (code "35") (name "Net-(D10-A)") (class "Default")
      (node (ref "D10") (pin "1") (pinfunction "A_1") (pintype "passive"))
      (node (ref "MX10") (pin "2") (pinfunction "ROW_2") (pintype "passive"))
    )
    (net (code "36") (name "Net-(D11-A)") (class "Default")
      (node (ref "D11") (pin "1") (pinfunction "A_1") (pintype "passive"))
      (node (ref "MX11") (pin "2") (pinfunction "ROW_2") (pintype "passive"))
    )
    (net (code "37") (name "Net-(D12-A)") (class "Default")
      (node (ref "D12") (pin "1") (pinfunction "A_1") (pintype "passive"))
      (node (ref "MX12") (pin "2") (pinfunction "ROW_2") (pintype "passive"))
    )
    (net (code "38") (name "Net-(D13-A)") (class "Default")
      (node (ref "D13") (pin "1") (pinfunction "A_1") (pintype "passive"))
      (node (ref "MX13") (pin "2") (pinfunction "ROW_2") (pintype "passive"))
    )
    (net (code "39") (name "Net-(D14-A)") (class "Default")
      (node (ref "D14") (pin "1") (pinfunction "A_1") (pintype "passive"))
      (node (ref "MX14") (pin "2") (pinfunction "ROW_2") (pintype "passive"))
    )
    (net (code "40") (name "Net-(D15-A)") (class "Default")
      (node (ref "D15") (pin "1") (pinfunction "A_1") (pintype "passive"))
      (node (ref "MX15") (pin "2") (pinfunction "ROW_2") (pintype "passive"))
    )
    (net (code "41") (name "Net-(D16-A)") (class "Default")
      (node (ref "D16") (pin "1") (pinfunction "A_1") (pintype "passive"))
      (node (ref "MX16") (pin "2") (pinfunction "ROW_2") (pintype "passive"))
    )
    (net (code "42") (name "Net-(D17-A)") (class "Default")
      (node (ref "D17") (pin "1") (pinfunction "A_1") (pintype "passive"))
      (node (ref "MX17") (pin "2") (pinfunction "ROW_2") (pintype "passive"))
    )
    (net (code "43") (name "Net-(D18-A)") (class "Default")
      (node (ref "D18") (pin "1") (pinfunction "A_1") (pintype "passive"))
      (node (ref "MX18") (pin "2") (pinfunction "ROW_2") (pintype "passive"))
    )
    (net (code "44") (name "Net-(D19-A)") (class "Default")
      (node (ref "D19") (pin "1") (pinfunction "A_1") (pintype "passive"))
      (node (ref "MX19") (pin "2") (pinfunction "ROW_2") (pintype "passive"))
    )
    (net (code "45") (name "Net-(D20-A)") (class "Default")
      (node (ref "D20") (pin "1") (pinfunction "A_1") (pintype "passive"))
      (node (ref "MX20") (pin "2") (pinfunction "ROW_2") (pintype "passive"))
    )
    (net (code "46") (name "Net-(D21-A)") (class "Default")
      (node (ref "D21") (pin "1") (pinfunction "A_1") (pintype "passive"))
      (node (ref "MX21") (pin "2") (pinfunction "ROW_2") (pintype "passive"))
    )
    (net (code "47") (name "Net-(D22-A)") (class "Default")
      (node (ref "D22") (pin "1") (pinfunction "A_1") (pintype "passive"))
      (node (ref "MX22") (pin "2") (pinfunction "ROW_2") (pintype "passive"))
    )
    (net (code "48") (name "Net-(D23-A)") (class "Default")
      (node (ref "D23") (pin "1") (pinfunction "A_1") (pintype "passive"))
      (node (ref "MX23") (pin "2") (pinfunction "ROW_2") (pintype "passive"))
    )
    (net (code "49") (name "Net-(D24-A)") (class "Default")
      (node (ref "D24") (pin "1") (pinfunction "A_1") (pintype "passive"))
      (node (ref "MX24") (pin "2") (pinfunction "ROW_2") (pintype "passive"))
    )
    (net (code "50") (name "Net-(D25-A)") (class "Default")
      (node (ref "D25") (pin "1") (pinfunction "A_1") (pintype "passive"))
      (node (ref "MX25") (pin "2") (pinfunction "ROW_2") (pintype "passive"))
    )
    (net (code "51") (name "Net-(D26-A)") (class "Default")
      (node (ref "D26") (pin "1") (pinfunction "A_1") (pintype "passive"))
      (node (ref "MX26") (pin "2") (pinfunction "ROW_2") (pintype "passive"))
    )
    (net (code "52") (name "Net-(D27-A)") (class "Default")
      (node (ref "D27") (pin "1") (pinfunction "A_1") (pintype "passive"))
      (node (ref "MX27") (pin "2") (pinfunction "ROW_2") (pintype "passive"))
    )
    (net (code "53") (name "Net-(D28-A)") (class "Default")
      (node (ref "D28") (pin "1") (pinfunction "A_1") (pintype "passive"))
      (node (ref "MX28") (pin "2") (pinfunction "ROW_2") (pintype "passive"))
    )
    (net (code "54") (name "Net-(D29-A)") (class "Default")
      (node (ref "D29") (pin "1") (pinfunction "A_1") (pintype "passive"))
      (node (ref "MX29") (pin "2") (pinfunction "ROW_2") (pintype "passive"))
    )
    (net (code "55") (name "Net-(D30-A)") (class "Default")
      (node (ref "D30") (pin "1") (pinfunction "A_1") (pintype "passive"))
      (node (ref "MX30") (pin "2") (pinfunction "ROW_2") (pintype "passive"))
    )
    (net (code "56") (name "Net-(D31-A)") (class "Default")
      (node (ref "D31") (pin "1") (pinfunction "A_1") (pintype "passive"))
      (node (ref "MX31") (pin "2") (pinfunction "ROW_2") (pintype "passive"))
    )
    (net (code "57") (name "Net-(D32-A)") (class "Default")
      (node (ref "D32") (pin "1") (pinfunction "A_1") (pintype "passive"))
      (node (ref "MX32") (pin "2") (pinfunction "ROW_2") (pintype "passive"))
    )
    (net (code "58") (name "Net-(D33-A)") (class "Default")
      (node (ref "D33") (pin "1") (pinfunction "A_1") (pintype "passive"))
      (node (ref "MX33") (pin "2") (pinfunction "ROW_2") (pintype "passive"))
    )
    (net (code "59") (name "Net-(D34-A)") (class "Default")
      (node (ref "D34") (pin "1") (pinfunction "A_1") (pintype "passive"))
      (node (ref "MX34") (pin "2") (pinfunction "ROW_2") (pintype "passive"))
    )
    (net (code "60") (name "Net-(D35-A)") (class "Default")
      (node (ref "D35") (pin "1") (pinfunction "A_1") (pintype "passive"))
      (node (ref "MX35") (pin "2") (pinfunction "ROW_2") (pintype "passive"))
    )
    (net (code "61") (name "Net-(D36-A)") (class "Default")
      (node (ref "D36") (pin "1") (pinfunction "A_1") (pintype "passive"))
      (node (ref "MX36") (pin "2") (pinfunction "ROW_2") (pintype "passive"))
    )
    (net (code "62") (name "Net-(D37-A)") (class "Default")
      (node (ref "D37") (pin "1") (pinfunction "A_1") (pintype "passive"))
      (node (ref "MX37") (pin "2") (pinfunction "ROW_2") (pintype "passive"))
    )
    (net (code "63") (name "Net-(D38-A)") (class "Default")
      (node (ref "D38") (pin "1") (pinfunction "A_1") (pintype "passive"))
      (node (ref "MX38") (pin "2") (pinfunction "ROW_2") (pintype "passive"))
    )
    (net (code "64") (name "Net-(D39-A)") (class "Default")
      (node (ref "D39") (pin "1") (pinfunction "A_1") (pintype "passive"))
      (node (ref "MX39") (pin "2") (pinfunction "ROW_2") (pintype "passive"))
    )
    (net (code "65") (name "Net-(D40-A)") (class "Default")
      (node (ref "D40") (pin "1") (pinfunction "A_1") (pintype "passive"))
      (node (ref "MX40") (pin "2") (pinfunction "ROW_2") (pintype "passive"))
    )
    (net (code "66") (name "Net-(D41-A)") (class "Default")
      (node (ref "D41") (pin "1") (pinfunction "A_1") (pintype "passive"))
      (node (ref "MX41") (pin "2") (pinfunction "ROW_2") (pintype "passive"))
    )
    (net (code "67") (name "Net-(D42-A)") (class "Default")
      (node (ref "D42") (pin "1") (pinfunction "A_1") (pintype "passive"))
      (node (ref "MX42") (pin "2") (pinfunction "ROW_2") (pintype "passive"))
    )
    (net (code "68") (name "Net-(D43-A)") (class "Default")
      (node (ref "D43") (pin "1") (pinfunction "A_1") (pintype "passive"))
      (node (ref "MX43") (pin "2") (pinfunction "ROW_2") (pintype "passive"))
    )
    (net (code "69") (name "Net-(D44-A)") (class "Default")
      (node (ref "D44") (pin "1") (pinfunction "A_1") (pintype "passive"))
      (node (ref "MX44") (pin "2") (pinfunction "ROW_2") (pintype "passive"))
    )
    (net (code "70") (name "Net-(D45-A)") (class "Default")
      (node (ref "D45") (pin "1") (pinfunction "A_1") (pintype "passive"))
      (node (ref "MX45") (pin "2") (pinfunction "ROW_2") (pintype "passive"))
    )
    (net (code "71") (name "Net-(D46-A)") (class "Default")
      (node (ref "D46") (pin "1") (pinfunction "A_1") (pintype "passive"))
      (node (ref "MX46") (pin "2") (pinfunction "ROW_2") (pintype "passive"))
    )
    (net (code "72") (name "Net-(D47-A)") (class "Default")
      (node (ref "D47") (pin "1") (pinfunction "A_1") (pintype "passive"))
      (node (ref "MX47") (pin "2") (pinfunction "ROW_2") (pintype "passive"))
    )
    (net (code "73") (name "Net-(D48-A)") (class "Default")
      (node (ref "D48") (pin "1") (pinfunction "A_1") (pintype "passive"))
      (node (ref "MX48") (pin "2") (pinfunction "ROW_2") (pintype "passive"))
    )
    (net (code "74") (name "Net-(D49-A)") (class "Default")
      (node (ref "D49") (pin "1") (pinfunction "A_1") (pintype "passive"))
      (node (ref "MX49") (pin "2") (pinfunction "ROW_2") (pintype "passive"))
    )
    (net (code "75") (name "Net-(D50-A)") (class "Default")
      (node (ref "D50") (pin "1") (pinfunction "A_1") (pintype "passive"))
      (node (ref "MX50") (pin "2") (pinfunction "ROW_2") (pintype "passive"))
    )
    (net (code "76") (name "Net-(D51-A)") (class "Default")
      (node (ref "D51") (pin "1") (pinfunction "A_1") (pintype "passive"))
      (node (ref "MX51") (pin "2") (pinfunction "ROW_2") (pintype "passive"))
    )
    (net (code "77") (name "Net-(D52-A)") (class "Default")
      (node (ref "D52") (pin "1") (pinfunction "A_1") (pintype "passive"))
      (node (ref "MX52") (pin "2") (pinfunction "ROW_2") (pintype "passive"))
    )
    (net (code "78") (name "Net-(D53-A)") (class "Default")
      (node (ref "D53") (pin "1") (pinfunction "A_1") (pintype "passive"))
      (node (ref "MX53") (pin "2") (pinfunction "ROW_2") (pintype "passive"))
    )
    (net (code "79") (name "Net-(D54-A)") (class "Default")
      (node (ref "D54") (pin "1") (pinfunction "A_1") (pintype "passive"))
      (node (ref "MX54") (pin "2") (pinfunction "ROW_2") (pintype "passive"))
    )
    (net (code "80") (name "Net-(D55-A)") (class "Default")
      (node (ref "D55") (pin "1") (pinfunction "A_1") (pintype "passive"))
      (node (ref "MX55") (pin "2") (pinfunction "ROW_2") (pintype "passive"))
    )
    (net (code "81") (name "Net-(D56-A)") (class "Default")
      (node (ref "D56") (pin "1") (pinfunction "A_1") (pintype "passive"))
      (node (ref "MX56") (pin "2") (pinfunction "ROW_2") (pintype "passive"))
    )
    (net (code "82") (name "Net-(D57-A)") (class "Default")
      (node (ref "D57") (pin "1") (pinfunction "A_1") (pintype "passive"))
      (node (ref "MX57") (pin "2") (pinfunction "ROW_2") (pintype "passive"))
    )
    (net (code "83") (name "Net-(D58-A)") (class "Default")
      (node (ref "D58") (pin "1") (pinfunction "A_1") (pintype "passive"))
      (node (ref "MX58") (pin "2") (pinfunction "ROW_2") (pintype "passive"))
    )
    (net (code "84") (name "Net-(D59-A)") (class "Default")
      (node (ref "D59") (pin "1") (pinfunction "A_1") (pintype "passive"))
      (node (ref "MX59") (pin "2") (pinfunction "ROW_2") (pintype "passive"))
    )
    (net (code "85") (name "Net-(D60-A)") (class "Default")
      (node (ref "D60") (pin "1") (pinfunction "A_1") (pintype "passive"))
      (node (ref "MX60") (pin "2") (pinfunction "ROW_2") (pintype "passive"))
    )
    (net (code "86") (name "Net-(D61-A)") (class "Default")
      (node (ref "D61") (pin "1") (pinfunction "A_1") (pintype "passive"))
      (node (ref "MX61") (pin "2") (pinfunction "ROW_2") (pintype "passive"))
    )
    (net (code "87") (name "Net-(D62-A)") (class "Default")
      (node (ref "D62") (pin "1") (pinfunction "A_1") (pintype "passive"))
      (node (ref "MX62") (pin "2") (pinfunction "ROW_2") (pintype "passive"))
    )
    (net (code "88") (name "Net-(D63-A)") (class "Default")
      (node (ref "D63") (pin "1") (pinfunction "A_1") (pintype "passive"))
      (node (ref "MX63") (pin "2") (pinfunction "ROW_2") (pintype "passive"))
    )
    (net (code "89") (name "Net-(D64-A)") (class "Default")
      (node (ref "D64") (pin "1") (pinfunction "A_1") (pintype "passive"))
      (node (ref "MX64") (pin "2") (pinfunction "ROW_2") (pintype "passive"))
    )
    (net (code "90") (name "Net-(D65-A)") (class "Default")
      (node (ref "D65") (pin "1") (pinfunction "A_1") (pintype "passive"))
      (node (ref "MX65") (pin "2") (pinfunction "ROW_2") (pintype "passive"))
    )
    (net (code "91") (name "Net-(D66-A)") (class "Default")
      (node (ref "D66") (pin "1") (pinfunction "A_1") (pintype "passive"))
      (node (ref "MX66") (pin "2") (pinfunction "ROW_2") (pintype "passive"))
    )
    (net (code "92") (name "Net-(D67-A)") (class "Default")
      (node (ref "D67") (pin "1") (pinfunction "A_1") (pintype "passive"))
      (node (ref "MX67") (pin "2") (pinfunction "ROW_2") (pintype "passive"))
    )
    (net (code "93") (name "Net-(D68-A)") (class "Default")
      (node (ref "D68") (pin "1") (pinfunction "A_1") (pintype "passive"))
      (node (ref "MX68") (pin "2") (pinfunction "ROW_2") (pintype "passive"))
    )
    (net (code "94") (name "Net-(D69-A)") (class "Default")
      (node (ref "D69") (pin "1") (pinfunction "A_1") (pintype "passive"))
      (node (ref "MX69") (pin "2") (pinfunction "ROW_2") (pintype "passive"))
    )
    (net (code "95") (name "Net-(D70-A)") (class "Default")
      (node (ref "D70") (pin "1") (pinfunction "A_1") (pintype "passive"))
      (node (ref "MX70") (pin "2") (pinfunction "ROW_2") (pintype "passive"))
    )
    (net (code "96") (name "Net-(D71-A)") (class "Default")
      (node (ref "D71") (pin "1") (pinfunction "A_1") (pintype "passive"))
      (node (ref "MX71") (pin "2") (pinfunction "ROW_2") (pintype "passive"))
    )
    (net (code "97") (name "Net-(D72-A)") (class "Default")
      (node (ref "D72") (pin "1") (pinfunction "A_1") (pintype "passive"))
      (node (ref "MX72") (pin "2") (pinfunction "ROW_2") (pintype "passive"))
    )
    (net (code "98") (name "Net-(D73-A)") (class "Default")
      (node (ref "D73") (pin "1") (pinfunction "A_1") (pintype "passive"))
      (node (ref "MX73") (pin "2") (pinfunction "ROW_2") (pintype "passive"))
    )
    (net (code "99") (name "Net-(D74-A)") (class "Default")
      (node (ref "D74") (pin "1") (pinfunction "A_1") (pintype "passive"))
      (node (ref "MX74") (pin "2") (pinfunction "ROW_2") (pintype "passive"))
    )
    (net (code "100") (name "Net-(D75-A)") (class "Default")
      (node (ref "D75") (pin "1") (pinfunction "A_1") (pintype "passive"))
      (node (ref "MX75") (pin "2") (pinfunction "ROW_2") (pintype "passive"))
    )
    (net (code "101") (name "Net-(D76-A)") (class "Default")
      (node (ref "D76") (pin "1") (pinfunction "A_1") (pintype "passive"))
      (node (ref "MX76") (pin "2") (pinfunction "ROW_2") (pintype "passive"))
    )
    (net (code "102") (name "Net-(D77-A)") (class "Default")
      (node (ref "D77") (pin "1") (pinfunction "A_1") (pintype "passive"))
      (node (ref "MX77") (pin "2") (pinfunction "ROW_2") (pintype "passive"))
    )
    (net (code "103") (name "Net-(D78-A)") (class "Default")
      (node (ref "D78") (pin "1") (pinfunction "A_1") (pintype "passive"))
      (node (ref "MX78") (pin "2") (pinfunction "ROW_2") (pintype "passive"))
    )
    (net (code "104") (name "Net-(D79-A)") (class "Default")
      (node (ref "D79") (pin "1") (pinfunction "A_1") (pintype "passive"))
      (node (ref "MX79") (pin "2") (pinfunction "ROW_2") (pintype "passive"))
    )
    (net (code "105") (name "Net-(D80-A)") (class "Default")
      (node (ref "D80") (pin "1") (pinfunction "A_1") (pintype "passive"))
      (node (ref "MX80") (pin "2") (pinfunction "ROW_2") (pintype "passive"))
    )
    (net (code "106") (name "Net-(D81-A)") (class "Default")
      (node (ref "D81") (pin "1") (pinfunction "A_1") (pintype "passive"))
      (node (ref "MX81") (pin "2") (pinfunction "ROW_2") (pintype "passive"))
    )
    (net (code "107") (name "Net-(D82-A)") (class "Default")
      (node (ref "D82") (pin "1") (pinfunction "A_1") (pintype "passive"))
      (node (ref "MX82") (pin "2") (pinfunction "ROW_2") (pintype "passive"))
    )
    (net (code "108") (name "Net-(D83-A)") (class "Default")
      (node (ref "D83") (pin "1") (pinfunction "A_1") (pintype "passive"))
      (node (ref "MX83") (pin "2") (pinfunction "ROW_2") (pintype "passive"))
    )
    (net (code "109") (name "Net-(D84-A)") (class "Default")
      (node (ref "D84") (pin "1") (pinfunction "A_1") (pintype "passive"))
      (node (ref "MX84") (pin "2") (pinfunction "ROW_2") (pintype "passive"))
    )
    (net (code "110") (name "Net-(D85-A)") (class "Default")
      (node (ref "D85") (pin "1") (pinfunction "A_1") (pintype "passive"))
      (node (ref "MX85") (pin "2") (pinfunction "ROW_2") (pintype "passive"))
    )
    (net (code "111") (name "Net-(D86-A)") (class "Default")
      (node (ref "D86") (pin "1") (pinfunction "A_1") (pintype "passive"))
      (node (ref "SW1") (pin "S2") (pinfunction "S2_S2") (pintype "passive"))
    )
  )
)
